# 3pdt.net
KiCad netlist of a schematic drawn in EAGLE
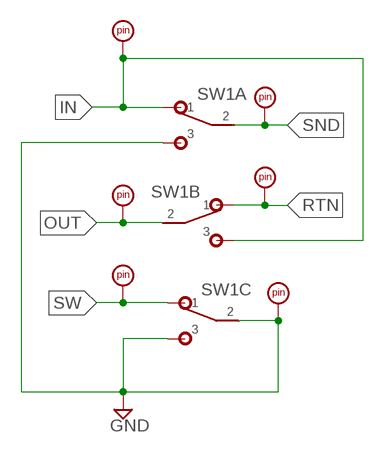
[diagram p0: schematic, sheet 1]

(export (version "E")
  (design (tool "Eeschema 10.0.6"))
  (components
    (comp (ref "GND")
      (value "PADRND")
      (footprint "eagle-import:ROUND")
      (libsource (lib "eagle-import") (part "PADRND"))
    )
    (comp (ref "IN")
      (value "PADSQR")
      (footprint "eagle-import:SQUARE")
      (libsource (lib "eagle-import") (part "PADSQR"))
    )
    (comp (ref "OUT")
      (value "PADSQR")
      (footprint "eagle-import:SQUARE")
      (libsource (lib "eagle-import") (part "PADSQR"))
    )
    (comp (ref "RTN")
      (value "PADSQR")
      (footprint "eagle-import:SQUARE")
      (libsource (lib "eagle-import") (part "PADSQR"))
    )
    (comp (ref "SND")
      (value "PADSQR")
      (footprint "eagle-import:SQUARE")
      (libsource (lib "eagle-import") (part "PADSQR"))
    )
    (comp (ref "SW")
      (value "PADRND")
      (footprint "eagle-import:ROUND")
      (libsource (lib "eagle-import") (part "PADRND"))
    )
    (comp (ref "SW1")
      (value "3PDT")
      (footprint "eagle-import:3PDT")
      (libsource (lib "eagle-import") (part "3PDT"))
    )
  )
  (nets
    (net (code "1") (name "GND") (class "Default")
      (node (ref "GND") (pin "1") (pinfunction "P$1_1") (pintype "bidirectional"))
      (node (ref "SW1") (pin "A3") (pinfunction "3_A3") (pintype "passive"))
      (node (ref "SW1") (pin "C2") (pinfunction "2_C2") (pintype "passive"))
      (node (ref "SW1") (pin "C3") (pinfunction "3_C3") (pintype "passive"))
    )
    (net (code "2") (name "IN") (class "Default")
      (node (ref "IN") (pin "1") (pinfunction "P$1_1") (pintype "bidirectional"))
      (node (ref "SW1") (pin "A1") (pinfunction "1_A1") (pintype "passive"))
      (node (ref "SW1") (pin "B3") (pinfunction "3_B3") (pintype "passive"))
    )
    (net (code "3") (name "OUT") (class "Default")
      (node (ref "OUT") (pin "1") (pinfunction "P$1_1") (pintype "bidirectional"))
      (node (ref "SW1") (pin "B2") (pinfunction "2_B2") (pintype "passive"))
    )
    (net (code "4") (name "RTN") (class "Default")
      (node (ref "RTN") (pin "1") (pinfunction "P$1_1") (pintype "bidirectional"))
      (node (ref "SW1") (pin "B1") (pinfunction "1_B1") (pintype "passive"))
    )
    (net (code "5") (name "SND") (class "Default")
      (node (ref "SND") (pin "1") (pinfunction "P$1_1") (pintype "bidirectional"))
      (node (ref "SW1") (pin "A2") (pinfunction "2_A2") (pintype "passive"))
    )
    (net (code "6") (name "SW") (class "Default")
      (node (ref "SW") (pin "1") (pinfunction "P$1_1") (pintype "bidirectional"))
      (node (ref "SW1") (pin "C1") (pinfunction "1_C1") (pintype "passive"))
    )
  )
)
